# HEADER.net
KiCad netlist of a schematic drawn in Altium Designer
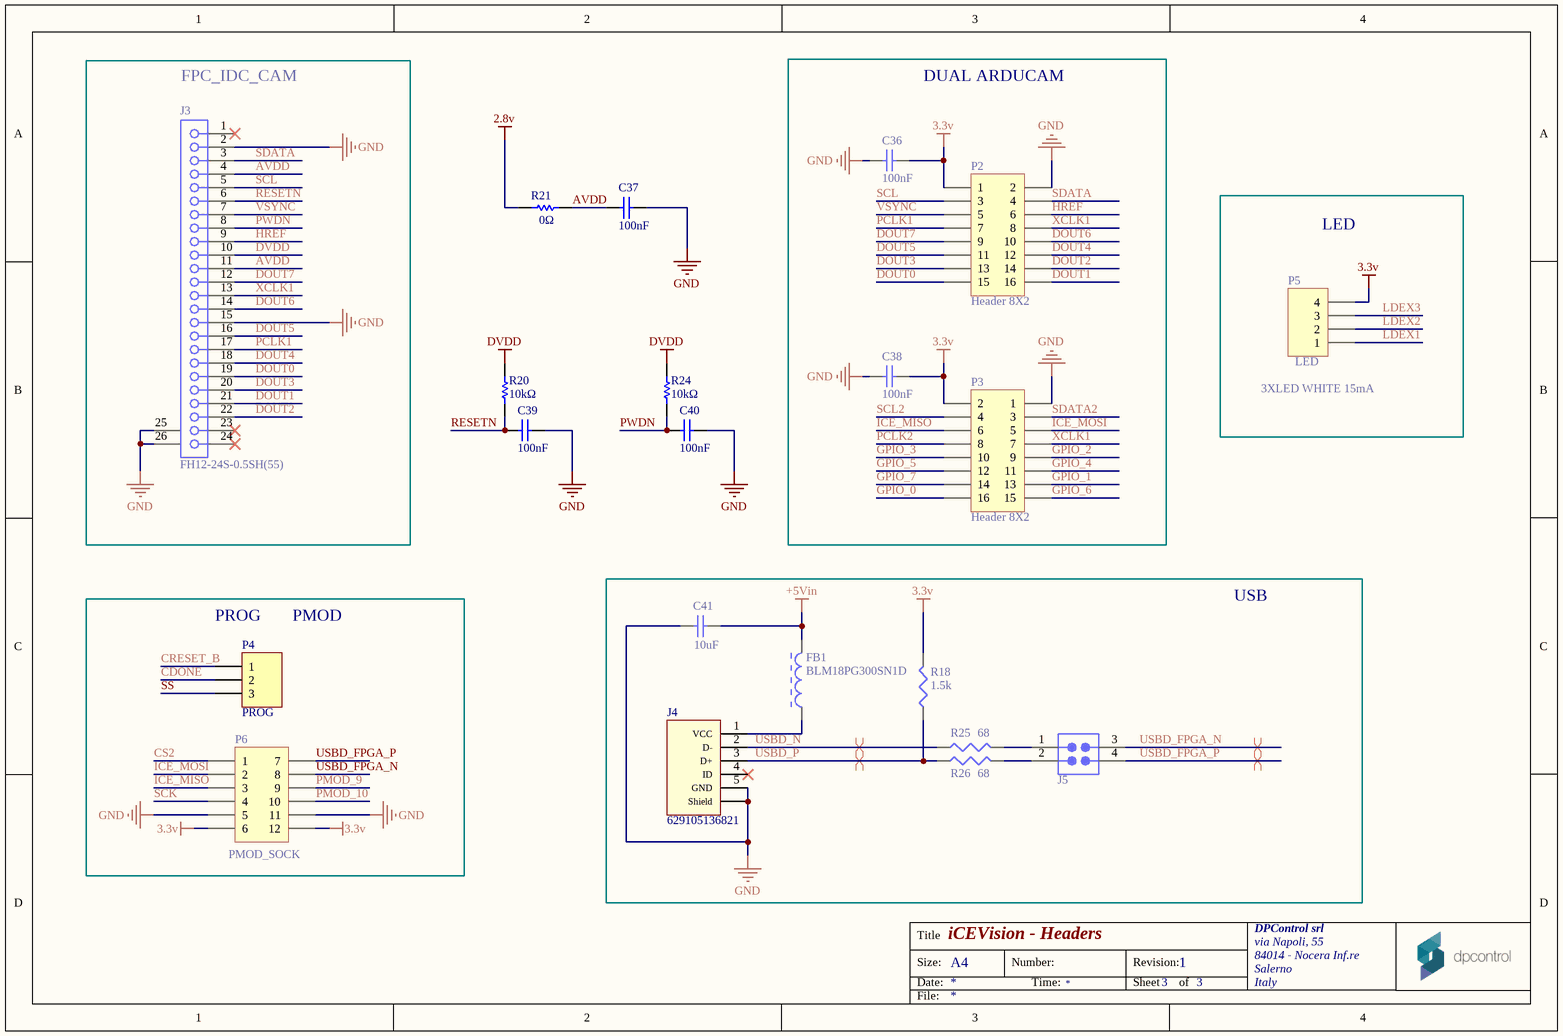
[diagram p0: HEADER.SchDoc]

(export (version "E")
  (design (tool "Eeschema 10.0.6"))
  (components
    (comp (ref "C36")
      (value "100nF")
      (footprint "0603")
      (description "Ceramic Chip Capacitor - Standard")
      (fields
        (field (name "PART NO") "C0603C104K8RACTU")
        (field (name "MPN") "GPC0603104")
        (field (name "PUBLISHER") "Altium Limited")
      )
      (libsource (lib "KEMET Chip Capacitor") (part "C0603"))
    )
    (comp (ref "C37")
      (value "100nF")
      (footprint "0603")
      (description "Ceramic Chip Capacitor - Standard")
      (fields
        (field (name "PART NO") "C0603C104K8RACTU")
        (field (name "MPN") "GPC0603104")
        (field (name "PUBLISHER") "Altium Limited")
      )
      (libsource (lib "KEMET Chip Capacitor") (part "C0603"))
    )
    (comp (ref "C38")
      (value "100nF")
      (footprint "0603")
      (description "Ceramic Chip Capacitor - Standard")
      (fields
        (field (name "PART NO") "C0603C104K8RACTU")
        (field (name "MPN") "GPC0603104")
        (field (name "PUBLISHER") "Altium Limited")
      )
      (libsource (lib "KEMET Chip Capacitor") (part "C0603"))
    )
    (comp (ref "C39")
      (value "100nF")
      (footprint "0603")
      (description "Ceramic Chip Capacitor - Standard")
      (fields
        (field (name "PART NO") "C0603C104K8RACTU")
        (field (name "MPN") "GPC0603104")
        (field (name "PUBLISHER") "Altium Limited")
      )
      (libsource (lib "KEMET Chip Capacitor") (part "C0603"))
    )
    (comp (ref "C40")
      (value "100nF")
      (footprint "0603")
      (description "Ceramic Chip Capacitor - Standard")
      (fields
        (field (name "PART NO") "C0603C104K8RACTU")
        (field (name "MPN") "GPC0603104")
        (field (name "PUBLISHER") "Altium Limited")
      )
      (libsource (lib "KEMET Chip Capacitor") (part "C0603"))
    )
    (comp (ref "C41")
      (value "10uF")
      (footprint "C1206")
      (description "Capacitor (Semiconductor SIM Model)")
      (fields
        (field (name "MPN") "1206ZD106KAT2A")
        (field (name "Comment") "Cap Semi")
        (field (name "PUBLISHER") "Altium Limited")
      )
      (libsource (lib "Miscellaneous Devices") (part "Cap Semi"))
    )
    (comp (ref "FB1")
      (value "BLM18PG300SN1D")
      (footprint "MURA-BLM18PG_KG-CHIP-2_V1")
      (fields (field (name "MANUFACTURER") "Murata"))
      (libsource (lib "altium-import") (part "root_1_MURA-FB-2_"))
    )
    (comp (ref "J3")
      (value "FH12-24S-0.5SH(55)")
      (footprint "FH12-24S-0.5SH")
      (description "FH12 Series, \"Flip-Lock\" SMT/ZIF FFC/FPC Connector - 0.5mm Spaced Bottom Contact")
      (fields (field (name "MPN") "FH12A-24S-0.5SH(55)") (field (name "PUBLISHER") "Altium Limited"))
      (libsource (lib "HRS FPC-FFC FH12 Series") (part "CL586-0521-0"))
    )
    (comp (ref "J4")
      (value "629105136821")
      (footprint "629105136821")
      (description "Micro USB 2.0 SMT Type B Horizontal 5 Contacts WR-COM")
      (fields (field (name "PUBLISHER") "Wurth Elektronik"))
      (libsource (lib "Altium_WR-COM (rev17a)") (part "629105136821"))
    )
    (comp (ref "J5")
      (value "WE-2.54 mm Pin Header & Jumper 61300421121")
      (footprint "61300421121")
      (description "WR-PHD 2.54 mm Dual Pin Header")
      (fields
        (field (name "MANUFACTURER") "Würth Elektronik eiSos GmbH")
        (field (name "PARTNO") "61300421121")
        (field (name "CREATED BY") "Karrer Zheng")
      )
      (libsource (lib "WE_WR-PHD_Pin Header_2.54mm_rev15c") (part "WE-2.54 mm Pin Header & Jumper 61300421121"))
    )
    (comp (ref "P2")
      (value "Header 8X2")
      (footprint "HDR2X8")
      (description "Header, 8-Pin, Dual row")
      (fields (field (name "PUBLISHER") "Altium Limited"))
      (libsource (lib "") (part "Header 8X2_1"))
    )
    (comp (ref "P3")
      (value "Header 8X2")
      (footprint "HDR2X8")
      (description "Header, 8-Pin, Dual row")
      (fields (field (name "PUBLISHER") "Altium Limited"))
      (libsource (lib "Miscellaneous Connectors") (part "Header 8X2"))
    )
    (comp (ref "P4")
      (value "PROG")
      (footprint "HDR1X3")
      (description "Header, 3-Pin")
      (fields (field (name "PUBLISHER") "Altium Limited"))
      (libsource (lib "Miscellaneous Connectors") (part "Header 3"))
    )
    (comp (ref "P5")
      (value "LED")
      (footprint "MHDR1X4")
      (description "Header, 4-Pin")
      (fields (field (name "PUBLISHER") "Altium Limited"))
      (libsource (lib "Miscellaneous Connectors") (part "MHDR1X4"))
    )
    (comp (ref "P6")
      (value "PMOD_SOCK")
      (footprint "HDR2X6_CEN")
      (description "Header, 6-Pin, Dual row")
      (fields (field (name "PUBLISHER") "Altium Limited"))
      (libsource (lib "Miscellaneous Connectors") (part "Header 6X2A"))
    )
    (comp (ref "R18")
      (value "1.5k")
      (footprint "J1-0603")
      (description "Resistor")
      (fields
        (field (name "MPN") "GPR06031K5")
        (field (name "Comment") "Res3")
        (field (name "PUBLISHER") "Altium Limited")
      )
      (libsource (lib "Miscellaneous Devices") (part "Res3"))
    )
    (comp (ref "R20")
      (value "10kΩ")
      (footprint "3-0603")
      (fields
        (field (name "PART NO") "ERJ3EKF1002V")
        (field (name "MPN") "GPR060310K")
        (field (name "Comment") "ERJ3EK")
        (field (name "PUBLISHER") "Altium Limited")
      )
      (libsource (lib "Panasonic Resistor") (part "ERJ3EK"))
    )
    (comp (ref "R21")
      (value "0Ω")
      (footprint "3-0603")
      (fields
        (field (name "PART NO") "ERJ3GEY0R00V")
        (field (name "MPN") "CRCW06030000Z0EA")
        (field (name "Comment") "ERJ3EK")
        (field (name "PUBLISHER") "Altium Limited")
      )
      (libsource (lib "Panasonic Resistor") (part "ERJ3EK"))
    )
    (comp (ref "R24")
      (value "10kΩ")
      (footprint "3-0603")
      (fields
        (field (name "PART NO") "ERJ3EKF1002V")
        (field (name "MPN") "GPR060310K")
        (field (name "Comment") "ERJ3EK")
        (field (name "PUBLISHER") "Altium Limited")
      )
      (libsource (lib "Panasonic Resistor") (part "ERJ3EK"))
    )
    (comp (ref "R25")
      (value "68")
      (footprint "J1-0603")
      (description "Resistor")
      (fields
        (field (name "MPN") "GPR060368R")
        (field (name "Comment") "Res3")
        (field (name "PUBLISHER") "Altium Limited")
      )
      (libsource (lib "Miscellaneous Devices") (part "Res3"))
    )
    (comp (ref "R26")
      (value "68")
      (footprint "J1-0603")
      (description "Resistor")
      (fields
        (field (name "MPN") "GPR060368R")
        (field (name "Comment") "Res3")
        (field (name "PUBLISHER") "Altium Limited")
      )
      (libsource (lib "Miscellaneous Devices") (part "Res3"))
    )
  )
  (nets
    (net (code "1") (name "+5Vin") (class "Default")
      (node (ref "C41") (pin "2") (pinfunction "2_2") (pintype "passive"))
      (node (ref "FB1") (pin "2") (pinfunction "2_2") (pintype "passive"))
    )
    (net (code "2") (name "/AVDD") (class "Default")
      (node (ref "C37") (pin "2") (pinfunction "2_2") (pintype "passive"))
      (node (ref "J3") (pin "11") (pinfunction "11_11") (pintype "passive"))
      (node (ref "J3") (pin "4") (pinfunction "4_4") (pintype "passive"))
      (node (ref "R21") (pin "2") (pinfunction "2_2") (pintype "passive"))
    )
    (net (code "3") (name "/CDONE") (class "Default")
      (node (ref "P4") (pin "2") (pinfunction "2_2") (pintype "passive"))
    )
    (net (code "4") (name "/CRESET_B") (class "Default")
      (node (ref "P4") (pin "1") (pinfunction "1_1") (pintype "passive"))
    )
    (net (code "5") (name "/CS2") (class "Default")
      (node (ref "P6") (pin "1") (pinfunction "1_1") (pintype "passive"))
    )
    (net (code "6") (name "/DOUT0") (class "Default")
      (node (ref "J3") (pin "19") (pinfunction "19_19") (pintype "passive"))
      (node (ref "P2") (pin "15") (pinfunction "15_15") (pintype "passive"))
    )
    (net (code "7") (name "/DOUT1") (class "Default")
      (node (ref "J3") (pin "21") (pinfunction "21_21") (pintype "passive"))
      (node (ref "P2") (pin "16") (pinfunction "16_16") (pintype "passive"))
    )
    (net (code "8") (name "/DOUT2") (class "Default")
      (node (ref "J3") (pin "22") (pinfunction "22_22") (pintype "passive"))
      (node (ref "P2") (pin "14") (pinfunction "14_14") (pintype "passive"))
    )
    (net (code "9") (name "/DOUT3") (class "Default")
      (node (ref "J3") (pin "20") (pinfunction "20_20") (pintype "passive"))
      (node (ref "P2") (pin "13") (pinfunction "13_13") (pintype "passive"))
    )
    (net (code "10") (name "/DOUT4") (class "Default")
      (node (ref "J3") (pin "18") (pinfunction "18_18") (pintype "passive"))
      (node (ref "P2") (pin "12") (pinfunction "12_12") (pintype "passive"))
    )
    (net (code "11") (name "/DOUT5") (class "Default")
      (node (ref "J3") (pin "16") (pinfunction "16_16") (pintype "passive"))
      (node (ref "P2") (pin "11") (pinfunction "11_11") (pintype "passive"))
    )
    (net (code "12") (name "/DOUT6") (class "Default")
      (node (ref "J3") (pin "14") (pinfunction "14_14") (pintype "passive"))
      (node (ref "P2") (pin "10") (pinfunction "10_10") (pintype "passive"))
    )
    (net (code "13") (name "/DOUT7") (class "Default")
      (node (ref "J3") (pin "12") (pinfunction "12_12") (pintype "passive"))
      (node (ref "P2") (pin "9") (pinfunction "9_9") (pintype "passive"))
    )
    (net (code "14") (name "/GPIO_0") (class "Default")
      (node (ref "P3") (pin "16") (pinfunction "16_16") (pintype "passive"))
    )
    (net (code "15") (name "/GPIO_1") (class "Default")
      (node (ref "P3") (pin "13") (pinfunction "13_13") (pintype "passive"))
    )
    (net (code "16") (name "/GPIO_2") (class "Default")
      (node (ref "P3") (pin "9") (pinfunction "9_9") (pintype "passive"))
    )
    (net (code "17") (name "/GPIO_3") (class "Default")
      (node (ref "P3") (pin "10") (pinfunction "10_10") (pintype "passive"))
    )
    (net (code "18") (name "/GPIO_4") (class "Default")
      (node (ref "P3") (pin "11") (pinfunction "11_11") (pintype "passive"))
    )
    (net (code "19") (name "/GPIO_5") (class "Default")
      (node (ref "P3") (pin "12") (pinfunction "12_12") (pintype "passive"))
    )
    (net (code "20") (name "/GPIO_6") (class "Default")
      (node (ref "P3") (pin "15") (pinfunction "15_15") (pintype "passive"))
    )
    (net (code "21") (name "/GPIO_7") (class "Default")
      (node (ref "P3") (pin "14") (pinfunction "14_14") (pintype "passive"))
    )
    (net (code "22") (name "/HREF") (class "Default")
      (node (ref "J3") (pin "9") (pinfunction "9_9") (pintype "passive"))
      (node (ref "P2") (pin "6") (pinfunction "6_6") (pintype "passive"))
    )
    (net (code "23") (name "/ICE_MISO") (class "Default")
      (node (ref "P3") (pin "6") (pinfunction "6_6") (pintype "passive"))
      (node (ref "P6") (pin "3") (pinfunction "3_3") (pintype "passive"))
    )
    (net (code "24") (name "/ICE_MOSI") (class "Default")
      (node (ref "P3") (pin "5") (pinfunction "5_5") (pintype "passive"))
      (node (ref "P6") (pin "2") (pinfunction "2_2") (pintype "passive"))
    )
    (net (code "25") (name "/LDEX1") (class "Default")
      (node (ref "P5") (pin "1") (pinfunction "1_1") (pintype "passive"))
    )
    (net (code "26") (name "/LDEX2") (class "Default")
      (node (ref "P5") (pin "2") (pinfunction "2_2") (pintype "passive"))
    )
    (net (code "27") (name "/LDEX3") (class "Default")
      (node (ref "P5") (pin "3") (pinfunction "3_3") (pintype "passive"))
    )
    (net (code "28") (name "/PCLK1") (class "Default")
      (node (ref "J3") (pin "17") (pinfunction "17_17") (pintype "passive"))
      (node (ref "P2") (pin "7") (pinfunction "7_7") (pintype "passive"))
    )
    (net (code "29") (name "/PCLK2") (class "Default")
      (node (ref "P3") (pin "8") (pinfunction "8_8") (pintype "passive"))
    )
    (net (code "30") (name "/PMOD_9") (class "Default")
      (node (ref "P6") (pin "9") (pinfunction "9_9") (pintype "passive"))
    )
    (net (code "31") (name "/PMOD_10") (class "Default")
      (node (ref "P6") (pin "10") (pinfunction "10_10") (pintype "passive"))
    )
    (net (code "32") (name "/PWDN") (class "Default")
      (node (ref "C40") (pin "2") (pinfunction "2_2") (pintype "passive"))
      (node (ref "J3") (pin "8") (pinfunction "8_8") (pintype "passive"))
      (node (ref "R24") (pin "1") (pinfunction "1_1") (pintype "passive"))
    )
    (net (code "33") (name "/RESETN") (class "Default")
      (node (ref "C39") (pin "2") (pinfunction "2_2") (pintype "passive"))
      (node (ref "J3") (pin "6") (pinfunction "6_6") (pintype "passive"))
      (node (ref "R20") (pin "1") (pinfunction "1_1") (pintype "passive"))
    )
    (net (code "34") (name "/SCK") (class "Default")
      (node (ref "P6") (pin "4") (pinfunction "4_4") (pintype "passive"))
    )
    (net (code "35") (name "/SCL") (class "Default")
      (node (ref "J3") (pin "5") (pinfunction "5_5") (pintype "passive"))
      (node (ref "P2") (pin "3") (pinfunction "3_3") (pintype "passive"))
    )
    (net (code "36") (name "/SCL2") (class "Default")
      (node (ref "P3") (pin "4") (pinfunction "4_4") (pintype "passive"))
    )
    (net (code "37") (name "/SDATA") (class "Default")
      (node (ref "J3") (pin "3") (pinfunction "3_3") (pintype "passive"))
      (node (ref "P2") (pin "4") (pinfunction "4_4") (pintype "passive"))
    )
    (net (code "38") (name "/SDATA2") (class "Default")
      (node (ref "P3") (pin "3") (pinfunction "3_3") (pintype "passive"))
    )
    (net (code "39") (name "/SS") (class "Default")
      (node (ref "P4") (pin "3") (pinfunction "3_3") (pintype "passive"))
    )
    (net (code "40") (name "/USBD_FPGA_N") (class "Default")
      (node (ref "J5") (pin "3") (pinfunction "3_3") (pintype "passive"))
      (node (ref "P6") (pin "8") (pinfunction "8_8") (pintype "passive"))
    )
    (net (code "41") (name "/USBD_FPGA_P") (class "Default")
      (node (ref "J5") (pin "4") (pinfunction "4_4") (pintype "passive"))
      (node (ref "P6") (pin "7") (pinfunction "7_7") (pintype "passive"))
    )
    (net (code "42") (name "/USBD_N") (class "Default")
      (node (ref "J4") (pin "2") (pinfunction "D-_2") (pintype "passive"))
      (node (ref "R25") (pin "1") (pinfunction "1_1") (pintype "passive"))
    )
    (net (code "43") (name "/USBD_P") (class "Default")
      (node (ref "J4") (pin "3") (pinfunction "D+_3") (pintype "passive"))
      (node (ref "R18") (pin "1") (pinfunction "1_1") (pintype "passive"))
      (node (ref "R26") (pin "1") (pinfunction "1_1") (pintype "passive"))
    )
    (net (code "44") (name "/VSYNC") (class "Default")
      (node (ref "J3") (pin "7") (pinfunction "7_7") (pintype "passive"))
      (node (ref "P2") (pin "5") (pinfunction "5_5") (pintype "passive"))
    )
    (net (code "45") (name "/XCLK1") (class "Default")
      (node (ref "J3") (pin "13") (pinfunction "13_13") (pintype "passive"))
      (node (ref "P2") (pin "8") (pinfunction "8_8") (pintype "passive"))
      (node (ref "P3") (pin "7") (pinfunction "7_7") (pintype "passive"))
    )
    (net (code "46") (name "2.8v") (class "Default")
      (node (ref "R21") (pin "1") (pinfunction "1_1") (pintype "passive"))
    )
    (net (code "47") (name "3.3v") (class "Default")
      (node (ref "C36") (pin "1") (pinfunction "1_1") (pintype "passive"))
      (node (ref "C38") (pin "1") (pinfunction "1_1") (pintype "passive"))
      (node (ref "P2") (pin "1") (pinfunction "1_1") (pintype "passive"))
      (node (ref "P3") (pin "2") (pinfunction "2_2") (pintype "passive"))
      (node (ref "P5") (pin "4") (pinfunction "4_4") (pintype "passive"))
      (node (ref "P6") (pin "12") (pinfunction "12_12") (pintype "passive"))
      (node (ref "P6") (pin "6") (pinfunction "6_6") (pintype "passive"))
      (node (ref "R18") (pin "2") (pinfunction "2_2") (pintype "passive"))
    )
    (net (code "48") (name "DVDD") (class "Default")
      (node (ref "J3") (pin "10") (pinfunction "10_10") (pintype "passive"))
      (node (ref "R20") (pin "2") (pinfunction "2_2") (pintype "passive"))
      (node (ref "R24") (pin "2") (pinfunction "2_2") (pintype "passive"))
    )
    (net (code "49") (name "GND") (class "Default")
      (node (ref "C36") (pin "2") (pinfunction "2_2") (pintype "passive"))
      (node (ref "C37") (pin "1") (pinfunction "1_1") (pintype "passive"))
      (node (ref "C38") (pin "2") (pinfunction "2_2") (pintype "passive"))
      (node (ref "C39") (pin "1") (pinfunction "1_1") (pintype "passive"))
      (node (ref "C40") (pin "1") (pinfunction "1_1") (pintype "passive"))
      (node (ref "C41") (pin "1") (pinfunction "1_1") (pintype "passive"))
      (node (ref "J3") (pin "15") (pinfunction "15_15") (pintype "passive"))
      (node (ref "J3") (pin "2") (pinfunction "2_2") (pintype "passive"))
      (node (ref "J3") (pin "25") (pinfunction "MH1_25") (pintype "passive"))
      (node (ref "J3") (pin "26") (pinfunction "MH2_26") (pintype "passive"))
      (node (ref "J4") (pin "5") (pinfunction "GND_5") (pintype "passive"))
      (node (ref "J4") (pin "Shell") (pinfunction "Shield_Shell") (pintype "passive"))
      (node (ref "P2") (pin "2") (pinfunction "2_2") (pintype "passive"))
      (node (ref "P3") (pin "1") (pinfunction "1_1") (pintype "passive"))
      (node (ref "P6") (pin "11") (pinfunction "11_11") (pintype "passive"))
      (node (ref "P6") (pin "5") (pinfunction "5_5") (pintype "passive"))
    )
    (net (code "50") (name "Net-(J4-VCC)") (class "Default")
      (node (ref "FB1") (pin "1") (pinfunction "1_1") (pintype "passive"))
      (node (ref "J4") (pin "1") (pinfunction "VCC_1") (pintype "passive"))
    )
    (net (code "51") (name "Net-(J5-1)") (class "Default")
      (node (ref "J5") (pin "2") (pinfunction "1_2") (pintype "passive"))
      (node (ref "R26") (pin "2") (pinfunction "2_2") (pintype "passive"))
    )
    (net (code "52") (name "Net-(J5-2)") (class "Default")
      (node (ref "J5") (pin "1") (pinfunction "2_1") (pintype "passive"))
      (node (ref "R25") (pin "2") (pinfunction "2_2") (pintype "passive"))
    )
    (net (code "53") (name "unconnected-(J3-Pad1)") (class "Default")
      (node (ref "J3") (pin "1") (pinfunction "1_1") (pintype "passive+no_connect"))
    )
    (net (code "54") (name "unconnected-(J3-Pad23)") (class "Default")
      (node (ref "J3") (pin "23") (pinfunction "23_23") (pintype "passive+no_connect"))
    )
    (net (code "55") (name "unconnected-(J3-Pad24)") (class "Default")
      (node (ref "J3") (pin "24") (pinfunction "24_24") (pintype "passive+no_connect"))
    )
    (net (code "56") (name "unconnected-(J4-ID-Pad4)") (class "Default")
      (node (ref "J4") (pin "4") (pinfunction "ID_4") (pintype "passive+no_connect"))
    )
  )
)
